# Power_v1.net
KiCad netlist of a schematic drawn in Altium Designer
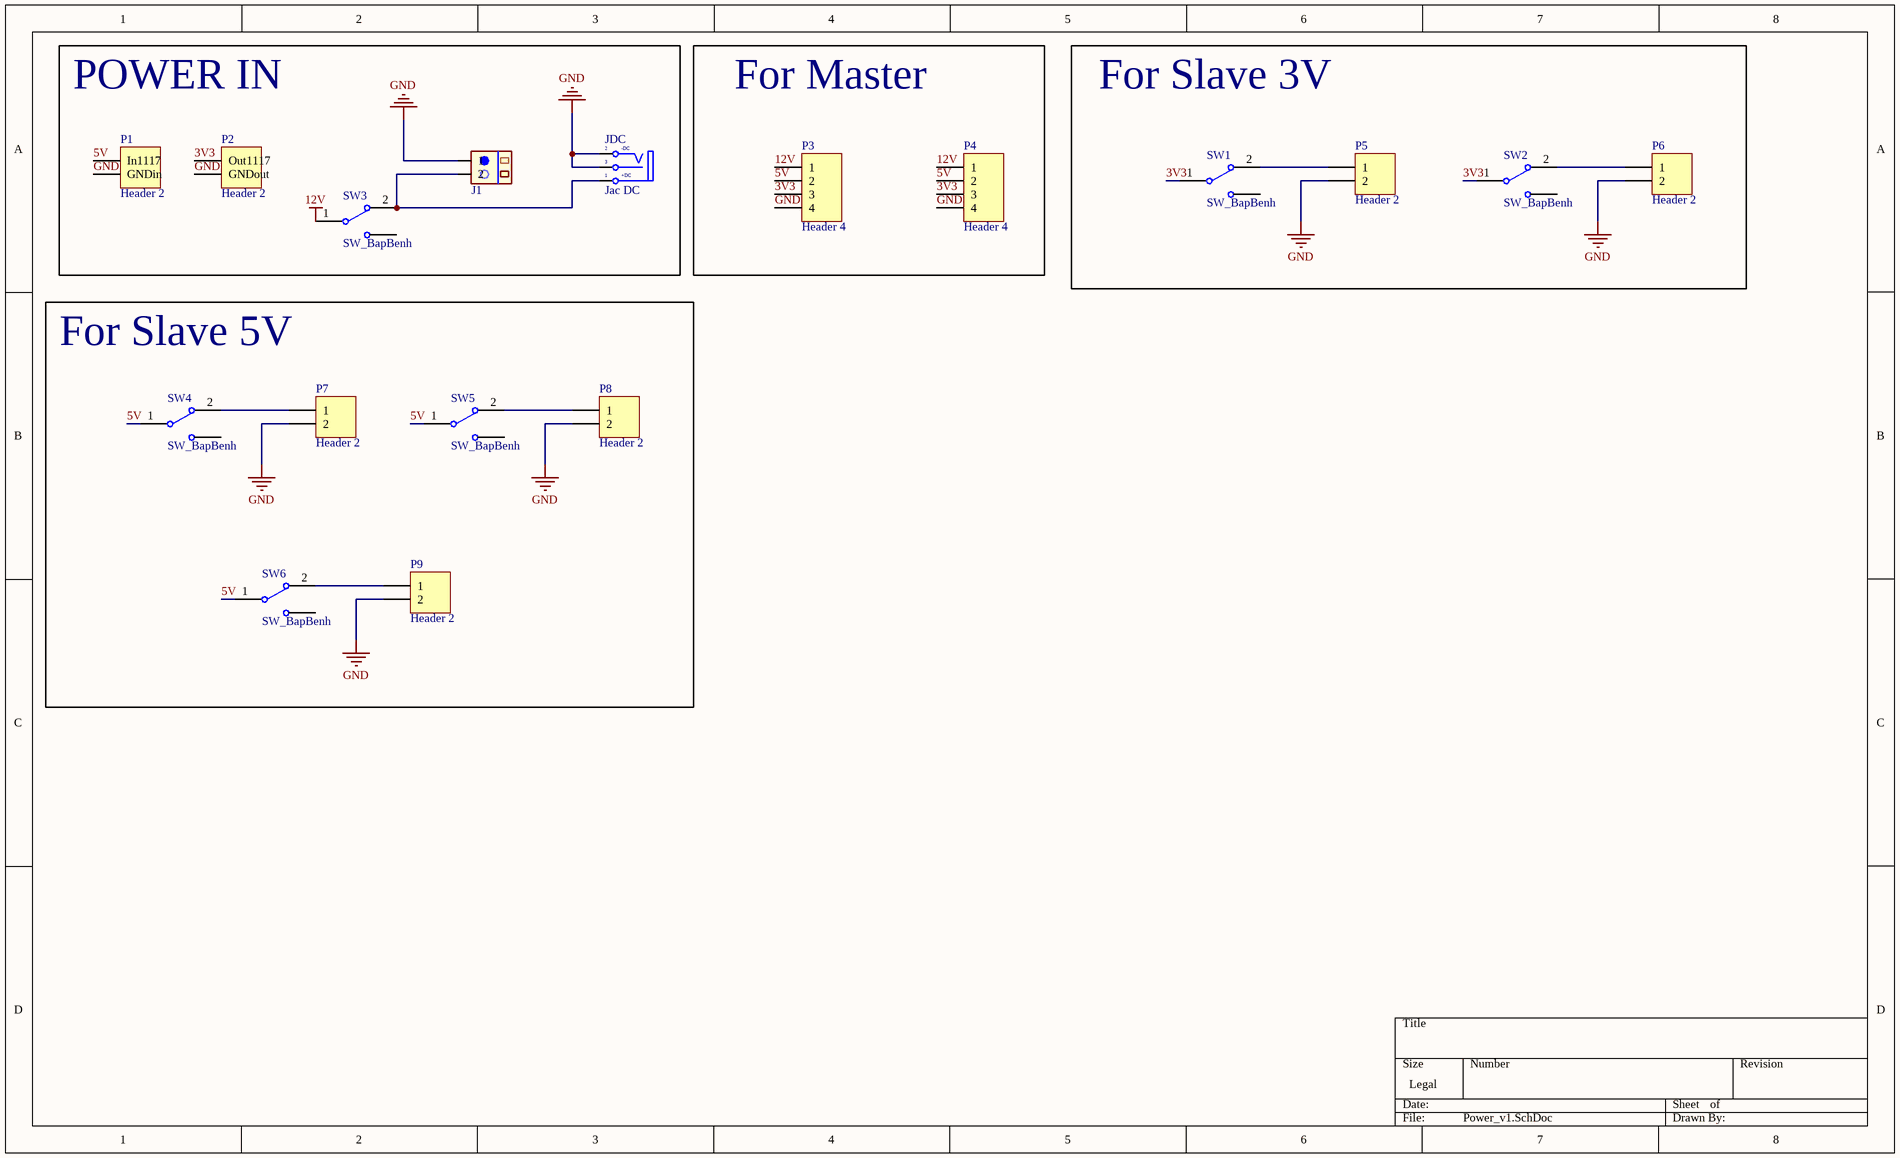
[diagram p0: Power_v1.SchDoc]

(export (version "E")
  (design (tool "Eeschema 10.0.6"))
  (components
    (comp (ref "J1")
      (value "CON.Domino2")
      (footprint "Domino 2M")
      (description "2 pins Domino Header")
      (fields (field (name "PUBLISHER") "Hoang Nguyen"))
      (libsource (lib "THG") (part "CON.Domino2"))
    )
    (comp (ref "JDC")
      (value "Jac DC")
      (footprint "DC-IN")
      (description "Jac DC input")
      (libsource (lib "hphonglib") (part "DCIN"))
    )
    (comp (ref "P1")
      (value "Header 2")
      (footprint "HDR1X2")
      (description "Header, 2-Pin")
      (fields (field (name "PUBLISHER") "Altium Limited"))
      (libsource (lib "Miscellaneous Connectors") (part "Header 2"))
    )
    (comp (ref "P2")
      (value "Header 2")
      (footprint "HDR1X2")
      (description "Header, 2-Pin")
      (fields (field (name "PUBLISHER") "Altium Limited"))
      (libsource (lib "Miscellaneous Connectors") (part "Header 2"))
    )
    (comp (ref "P3")
      (value "Header 4")
      (footprint "Header 4")
      (description "Header, 4-Pin")
      (fields (field (name "PUBLISHER") "Altium Limited"))
      (libsource (lib "THG") (part "Header 4"))
    )
    (comp (ref "P4")
      (value "Header 4")
      (footprint "Header 4")
      (description "Header, 4-Pin")
      (fields (field (name "PUBLISHER") "Altium Limited"))
      (libsource (lib "THG") (part "Header 4"))
    )
    (comp (ref "P5")
      (value "Header 2")
      (footprint "Header 2")
      (description "Header, 2-Pin")
      (fields (field (name "PUBLISHER") "Altium Limited"))
      (libsource (lib "THG") (part "Header 2"))
    )
    (comp (ref "P6")
      (value "Header 2")
      (footprint "Header 2")
      (description "Header, 2-Pin")
      (fields (field (name "PUBLISHER") "Altium Limited"))
      (libsource (lib "THG") (part "Header 2"))
    )
    (comp (ref "P7")
      (value "Header 2")
      (footprint "Header 2")
      (description "Header, 2-Pin")
      (fields (field (name "PUBLISHER") "Altium Limited"))
      (libsource (lib "THG") (part "Header 2"))
    )
    (comp (ref "P8")
      (value "Header 2")
      (footprint "Header 2")
      (description "Header, 2-Pin")
      (fields (field (name "PUBLISHER") "Altium Limited"))
      (libsource (lib "THG") (part "Header 2"))
    )
    (comp (ref "P9")
      (value "Header 2")
      (footprint "Header 2")
      (description "Header, 2-Pin")
      (fields (field (name "PUBLISHER") "Altium Limited"))
      (libsource (lib "THG") (part "Header 2"))
    )
    (comp (ref "SW1")
      (value "SW_BapBenh")
      (footprint "SW_Bapbenh")
      (libsource (lib "THG") (part "SW_BapBenh"))
    )
    (comp (ref "SW2")
      (value "SW_BapBenh")
      (footprint "SW_Bapbenh")
      (libsource (lib "THG") (part "SW_BapBenh"))
    )
    (comp (ref "SW3")
      (value "SW_BapBenh")
      (footprint "SW_Bapbenh")
      (libsource (lib "THG") (part "SW_BapBenh"))
    )
    (comp (ref "SW4")
      (value "SW_BapBenh")
      (footprint "SW_Bapbenh")
      (libsource (lib "THG") (part "SW_BapBenh"))
    )
    (comp (ref "SW5")
      (value "SW_BapBenh")
      (footprint "SW_Bapbenh")
      (libsource (lib "THG") (part "SW_BapBenh"))
    )
    (comp (ref "SW6")
      (value "SW_BapBenh")
      (footprint "SW_Bapbenh")
      (libsource (lib "THG") (part "SW_BapBenh"))
    )
  )
  (nets
    (net (code "1") (name "/3V3") (class "Default")
      (node (ref "P2") (pin "1") (pinfunction "In1117_1") (pintype "passive"))
      (node (ref "P3") (pin "3") (pinfunction "3_3") (pintype "passive"))
      (node (ref "P4") (pin "3") (pinfunction "3_3") (pintype "passive"))
      (node (ref "SW1") (pin "1") (pinfunction "1_1") (pintype "passive"))
      (node (ref "SW2") (pin "1") (pinfunction "1_1") (pintype "passive"))
    )
    (net (code "2") (name "/5V") (class "Default")
      (node (ref "P1") (pin "1") (pinfunction "In1117_1") (pintype "passive"))
      (node (ref "P3") (pin "2") (pinfunction "2_2") (pintype "passive"))
      (node (ref "P4") (pin "2") (pinfunction "2_2") (pintype "passive"))
      (node (ref "SW4") (pin "1") (pinfunction "1_1") (pintype "passive"))
      (node (ref "SW5") (pin "1") (pinfunction "1_1") (pintype "passive"))
      (node (ref "SW6") (pin "1") (pinfunction "1_1") (pintype "passive"))
    )
    (net (code "3") (name "12V") (class "Default")
      (node (ref "P3") (pin "1") (pinfunction "1_1") (pintype "passive"))
      (node (ref "P4") (pin "1") (pinfunction "1_1") (pintype "passive"))
      (node (ref "SW3") (pin "1") (pinfunction "1_1") (pintype "passive"))
    )
    (net (code "4") (name "GND") (class "Default")
      (node (ref "J1") (pin "1") (pinfunction "1_1") (pintype "passive"))
      (node (ref "JDC") (pin "2") (pinfunction "TN_2") (pintype "passive"))
      (node (ref "JDC") (pin "3") (pinfunction "S_3") (pintype "power_in"))
      (node (ref "P1") (pin "2") (pinfunction "GNDin_2") (pintype "passive"))
      (node (ref "P2") (pin "2") (pinfunction "GNDin_2") (pintype "passive"))
      (node (ref "P3") (pin "4") (pinfunction "4_4") (pintype "passive"))
      (node (ref "P4") (pin "4") (pinfunction "4_4") (pintype "passive"))
      (node (ref "P5") (pin "2") (pinfunction "2_2") (pintype "passive"))
      (node (ref "P6") (pin "2") (pinfunction "2_2") (pintype "passive"))
      (node (ref "P7") (pin "2") (pinfunction "2_2") (pintype "passive"))
      (node (ref "P8") (pin "2") (pinfunction "2_2") (pintype "passive"))
      (node (ref "P9") (pin "2") (pinfunction "2_2") (pintype "passive"))
    )
    (net (code "5") (name "Net-(JDC-T)") (class "Default")
      (node (ref "J1") (pin "2") (pinfunction "2_2") (pintype "passive"))
      (node (ref "JDC") (pin "1") (pinfunction "T_1") (pintype "passive"))
      (node (ref "SW3") (pin "2") (pinfunction "2_2") (pintype "passive"))
    )
    (net (code "6") (name "Net-(P5-Pad1)") (class "Default")
      (node (ref "P5") (pin "1") (pinfunction "1_1") (pintype "passive"))
      (node (ref "SW1") (pin "2") (pinfunction "2_2") (pintype "passive"))
    )
    (net (code "7") (name "Net-(P6-Pad1)") (class "Default")
      (node (ref "P6") (pin "1") (pinfunction "1_1") (pintype "passive"))
      (node (ref "SW2") (pin "2") (pinfunction "2_2") (pintype "passive"))
    )
    (net (code "8") (name "Net-(P7-Pad1)") (class "Default")
      (node (ref "P7") (pin "1") (pinfunction "1_1") (pintype "passive"))
      (node (ref "SW4") (pin "2") (pinfunction "2_2") (pintype "passive"))
    )
    (net (code "9") (name "Net-(P8-Pad1)") (class "Default")
      (node (ref "P8") (pin "1") (pinfunction "1_1") (pintype "passive"))
      (node (ref "SW5") (pin "2") (pinfunction "2_2") (pintype "passive"))
    )
    (net (code "10") (name "Net-(P9-Pad1)") (class "Default")
      (node (ref "P9") (pin "1") (pinfunction "1_1") (pintype "passive"))
      (node (ref "SW6") (pin "2") (pinfunction "2_2") (pintype "passive"))
    )
  )
)
